# middleman_pcb.net
KiCad netlist of a schematic drawn in EAGLE
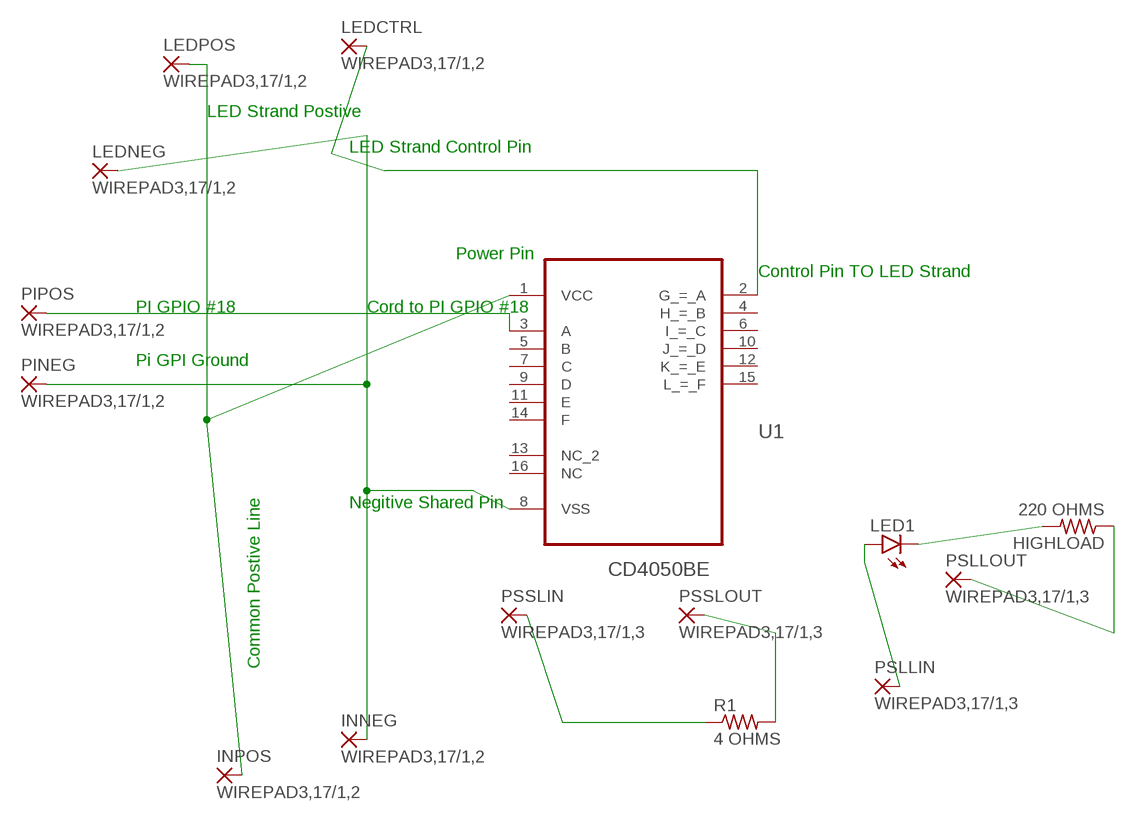
[diagram p0: schematic, sheet 1]

(export (version "E")
  (design (tool "Eeschema 10.0.6"))
  (components
    (comp (ref "HIGHLOAD")
      (value "220 OHMS")
      (footprint "eagle-import:R0805")
      (libsource (lib "eagle-import") (part "R-US_R0805"))
    )
    (comp (ref "INNEG")
      (value "WIREPAD3,17/1,2")
      (footprint "eagle-import:3,17_1,2")
      (libsource (lib "eagle-import") (part "WIREPAD3,17/1,2"))
    )
    (comp (ref "INPOS")
      (value "WIREPAD3,17/1,2")
      (footprint "eagle-import:3,17_1,2")
      (libsource (lib "eagle-import") (part "WIREPAD3,17/1,2"))
    )
    (comp (ref "LED1")
      (value "LED3MM")
      (footprint "eagle-import:LED3MM")
      (libsource (lib "eagle-import") (part "LED3MM"))
    )
    (comp (ref "LEDCTRL")
      (value "WIREPAD3,17/1,2")
      (footprint "eagle-import:3,17_1,2")
      (libsource (lib "eagle-import") (part "WIREPAD3,17/1,2"))
    )
    (comp (ref "LEDNEG")
      (value "WIREPAD3,17/1,2")
      (footprint "eagle-import:3,17_1,2")
      (libsource (lib "eagle-import") (part "WIREPAD3,17/1,2"))
    )
    (comp (ref "LEDPOS")
      (value "WIREPAD3,17/1,2")
      (footprint "eagle-import:3,17_1,2")
      (libsource (lib "eagle-import") (part "WIREPAD3,17/1,2"))
    )
    (comp (ref "PINEG")
      (value "WIREPAD3,17/1,2")
      (footprint "eagle-import:3,17_1,2")
      (libsource (lib "eagle-import") (part "WIREPAD3,17/1,2"))
    )
    (comp (ref "PIPOS")
      (value "WIREPAD3,17/1,2")
      (footprint "eagle-import:3,17_1,2")
      (libsource (lib "eagle-import") (part "WIREPAD3,17/1,2"))
    )
    (comp (ref "PSLLIN")
      (value "WIREPAD3,17/1,3")
      (footprint "eagle-import:3,17_1,3")
      (libsource (lib "eagle-import") (part "WIREPAD3,17/1,3"))
    )
    (comp (ref "PSLLOUT")
      (value "WIREPAD3,17/1,3")
      (footprint "eagle-import:3,17_1,3")
      (libsource (lib "eagle-import") (part "WIREPAD3,17/1,3"))
    )
    (comp (ref "PSSLIN")
      (value "WIREPAD3,17/1,3")
      (footprint "eagle-import:3,17_1,3")
      (libsource (lib "eagle-import") (part "WIREPAD3,17/1,3"))
    )
    (comp (ref "PSSLOUT")
      (value "WIREPAD3,17/1,3")
      (footprint "eagle-import:3,17_1,3")
      (libsource (lib "eagle-import") (part "WIREPAD3,17/1,3"))
    )
    (comp (ref "R1")
      (value "4 OHMS")
      (footprint "eagle-import:R0805")
      (libsource (lib "eagle-import") (part "R-US_R0805"))
    )
    (comp (ref "U1")
      (value "CD4050BE")
      (footprint "eagle-import:DIP254P762X508-16")
      (fields (field (name "MF") "Texas Instruments"))
      (libsource (lib "eagle-import") (part "CD4050BE"))
    )
  )
  (nets
    (net (code "1") (name "Net-(INNEG-P)") (class "Default")
      (node (ref "INNEG") (pin "1") (pinfunction "P_1") (pintype "passive"))
      (node (ref "LEDNEG") (pin "1") (pinfunction "P_1") (pintype "passive"))
      (node (ref "PINEG") (pin "1") (pinfunction "P_1") (pintype "passive"))
      (node (ref "U1") (pin "8") (pinfunction "VSS_8") (pintype "power_in"))
    )
    (net (code "2") (name "Net-(INPOS-P)") (class "Default")
      (node (ref "INPOS") (pin "1") (pinfunction "P_1") (pintype "passive"))
      (node (ref "LEDPOS") (pin "1") (pinfunction "P_1") (pintype "passive"))
      (node (ref "U1") (pin "1") (pinfunction "VCC_1") (pintype "power_in"))
    )
    (net (code "3") (name "Net-(LED1-C)") (class "Default")
      (node (ref "HIGHLOAD") (pin "2") (pinfunction "2_2") (pintype "passive"))
      (node (ref "LED1") (pin "K") (pinfunction "C_K") (pintype "passive"))
    )
    (net (code "4") (name "Net-(LEDCTRL-P)") (class "Default")
      (node (ref "LEDCTRL") (pin "1") (pinfunction "P_1") (pintype "passive"))
      (node (ref "U1") (pin "2") (pinfunction "G_=_A_2") (pintype "output"))
    )
    (net (code "5") (name "Net-(PIPOS-P)") (class "Default")
      (node (ref "PIPOS") (pin "1") (pinfunction "P_1") (pintype "passive"))
      (node (ref "U1") (pin "3") (pinfunction "A_3") (pintype "input"))
    )
    (net (code "6") (name "Net-(PSLLIN-P)") (class "Default")
      (node (ref "LED1") (pin "A") (pinfunction "A_A") (pintype "passive"))
      (node (ref "PSLLIN") (pin "1") (pinfunction "P_1") (pintype "passive"))
    )
    (net (code "7") (name "Net-(PSLLOUT-P)") (class "Default")
      (node (ref "HIGHLOAD") (pin "1") (pinfunction "1_1") (pintype "passive"))
      (node (ref "PSLLOUT") (pin "1") (pinfunction "P_1") (pintype "passive"))
    )
    (net (code "8") (name "Net-(PSSLIN-P)") (class "Default")
      (node (ref "PSSLIN") (pin "1") (pinfunction "P_1") (pintype "passive"))
      (node (ref "R1") (pin "1") (pinfunction "1_1") (pintype "passive"))
    )
    (net (code "9") (name "Net-(PSSLOUT-P)") (class "Default")
      (node (ref "PSSLOUT") (pin "1") (pinfunction "P_1") (pintype "passive"))
      (node (ref "R1") (pin "2") (pinfunction "2_2") (pintype "passive"))
    )
    (net (code "10") (name "unconnected-(U1-B-Pad5)") (class "Default")
      (node (ref "U1") (pin "5") (pinfunction "B_5") (pintype "input"))
    )
    (net (code "11") (name "unconnected-(U1-C-Pad7)") (class "Default")
      (node (ref "U1") (pin "7") (pinfunction "C_7") (pintype "input"))
    )
    (net (code "12") (name "unconnected-(U1-D-Pad9)") (class "Default")
      (node (ref "U1") (pin "9") (pinfunction "D_9") (pintype "input"))
    )
    (net (code "13") (name "unconnected-(U1-E-Pad11)") (class "Default")
      (node (ref "U1") (pin "11") (pinfunction "E_11") (pintype "input"))
    )
    (net (code "14") (name "unconnected-(U1-F-Pad14)") (class "Default")
      (node (ref "U1") (pin "14") (pinfunction "F_14") (pintype "input"))
    )
    (net (code "15") (name "unconnected-(U1-H_=_B-Pad4)") (class "Default")
      (node (ref "U1") (pin "4") (pinfunction "H_=_B_4") (pintype "output"))
    )
    (net (code "16") (name "unconnected-(U1-I_=_C-Pad6)") (class "Default")
      (node (ref "U1") (pin "6") (pinfunction "I_=_C_6") (pintype "output"))
    )
    (net (code "17") (name "unconnected-(U1-J_=_D-Pad10)") (class "Default")
      (node (ref "U1") (pin "10") (pinfunction "J_=_D_10") (pintype "output"))
    )
    (net (code "18") (name "unconnected-(U1-K_=_E-Pad12)") (class "Default")
      (node (ref "U1") (pin "12") (pinfunction "K_=_E_12") (pintype "output"))
    )
    (net (code "19") (name "unconnected-(U1-L_=_F-Pad15)") (class "Default")
      (node (ref "U1") (pin "15") (pinfunction "L_=_F_15") (pintype "output"))
    )
    (net (code "20") (name "unconnected-(U1-NC-Pad16)") (class "Default")
      (node (ref "U1") (pin "16") (pinfunction "NC_16") (pintype "no_connect"))
    )
    (net (code "21") (name "unconnected-(U1-NC_2-Pad13)") (class "Default")
      (node (ref "U1") (pin "13") (pinfunction "NC_2_13") (pintype "no_connect"))
    )
  )
)
